# pcb_optica.net
KiCad netlist of a schematic drawn in EasyEDA Pro
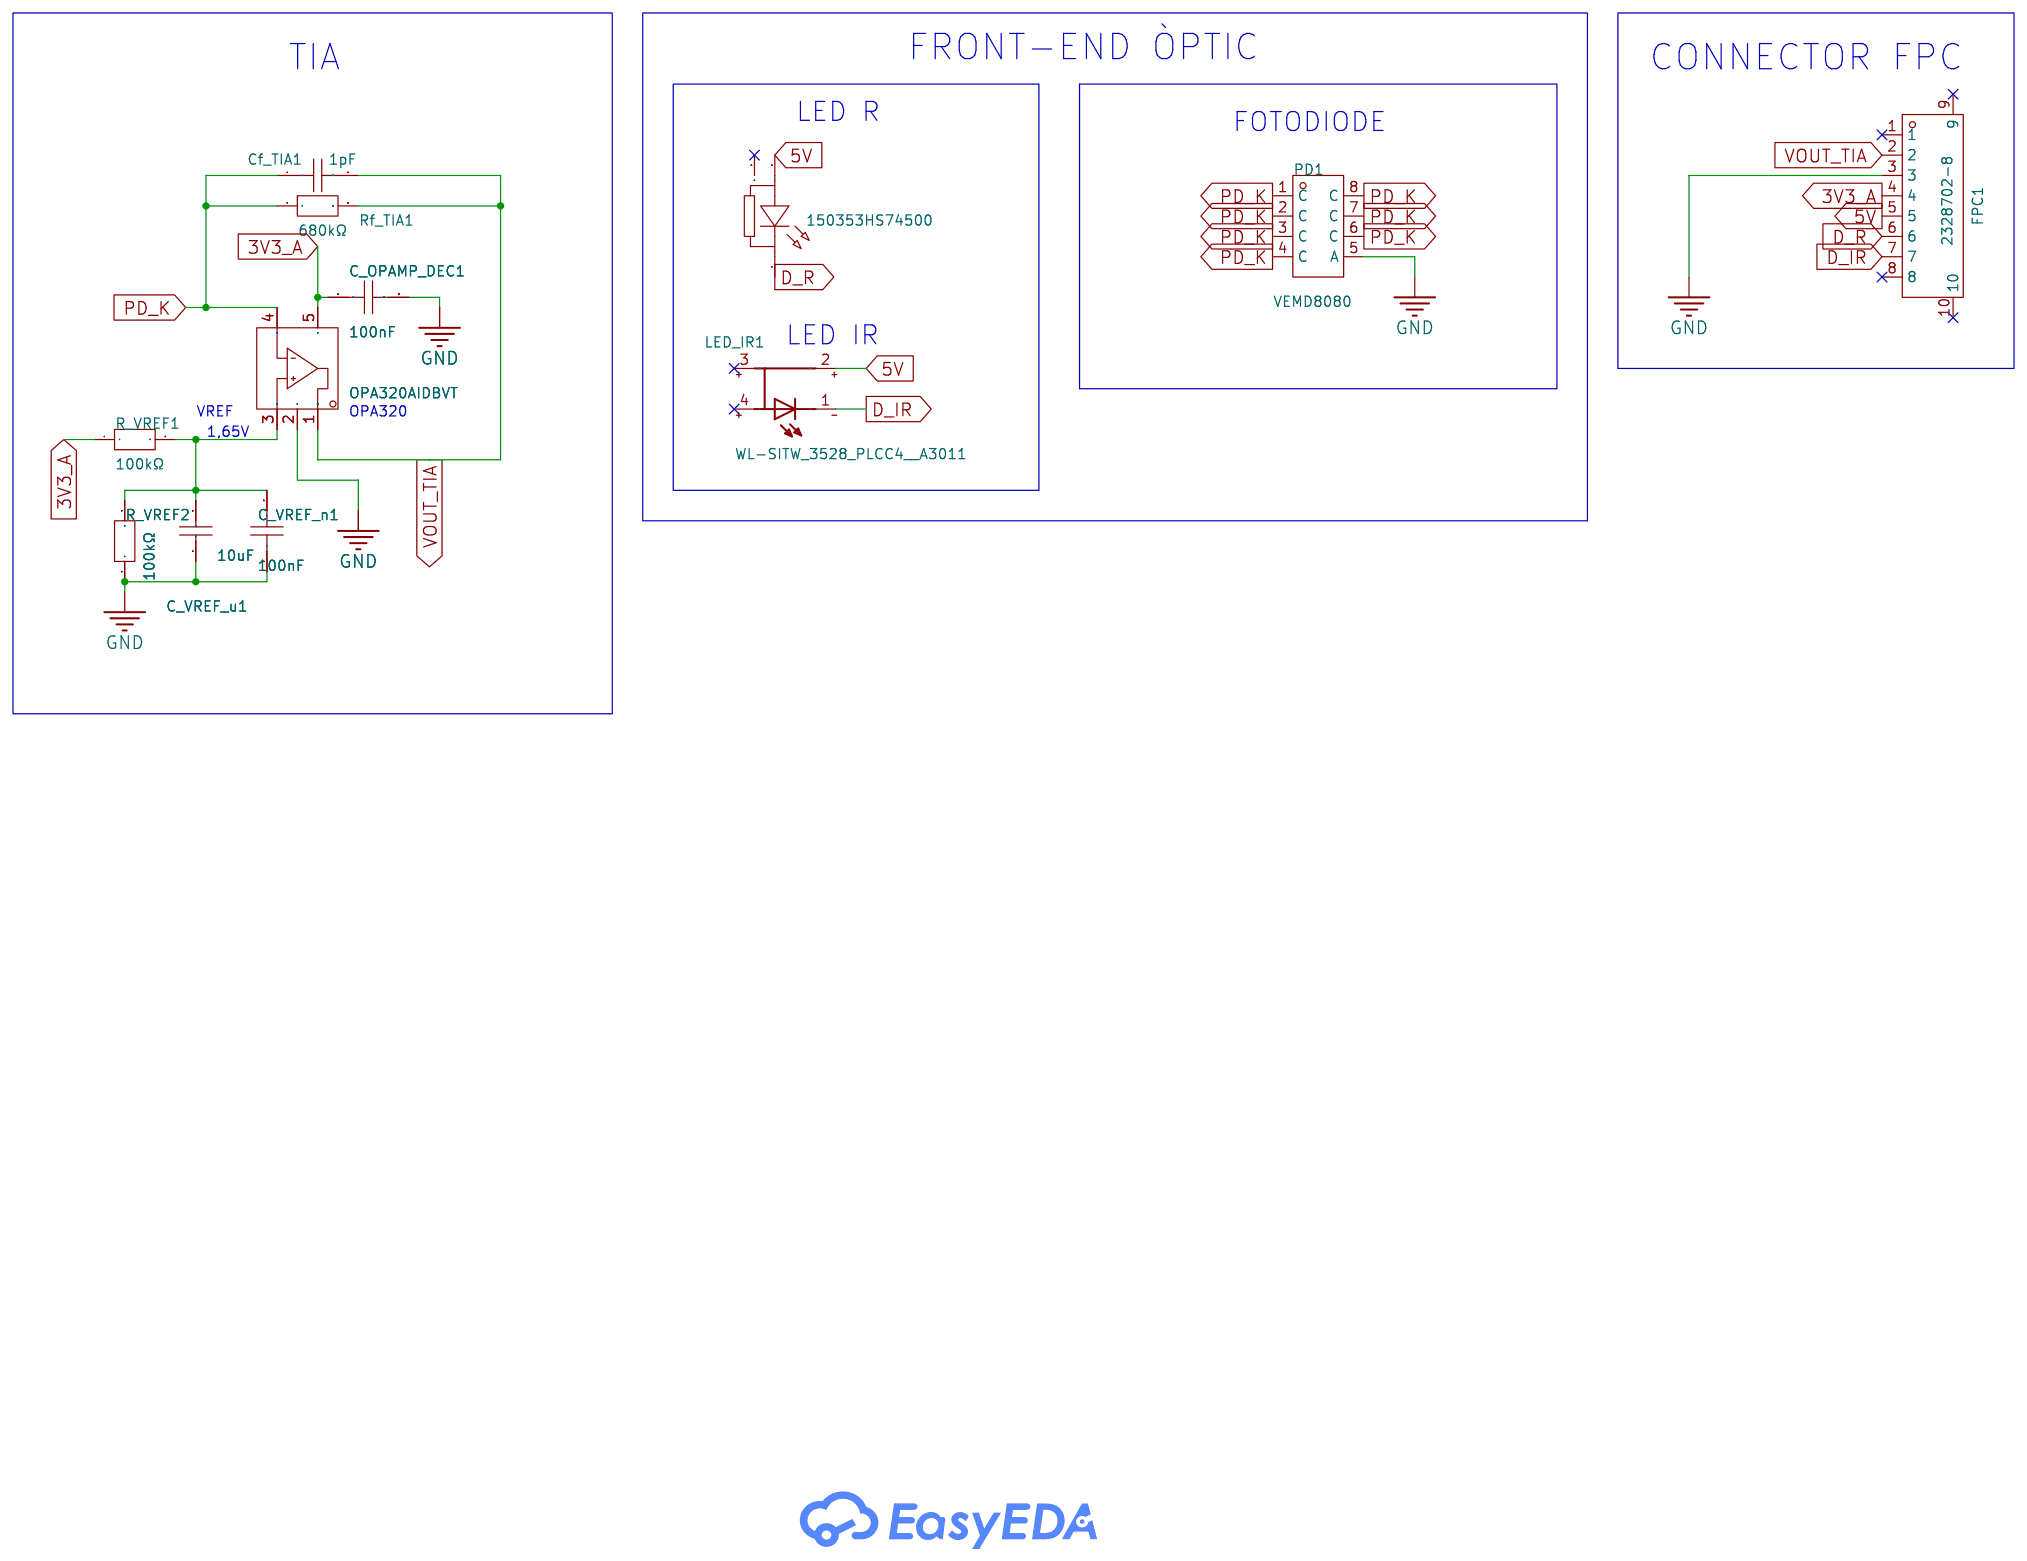
[diagram p0: schematic sheet]

(export (version "E")
  (design (tool "Eeschema 10.0.6"))
  (components
    (comp (ref "Cf_TIA1")
      (value "1pF")
      (footprint "easyedapro:C0805")
      (fields
        (field (name "Manufacturer Part") "CC0805BRNPO9BN1R0")
        (field (name "Manufacturer") "YAGEO(国巨)")
      )
      (libsource (lib "easyedapro") (part "CC0805BRNPO9BN1R0"))
    )
    (comp (ref "C_OPAMP_DEC1")
      (value "100nF")
      (footprint "easyedapro:C0805")
      (description "Capacitance:100nF Tolerance:±10% Tolerance:±10% Voltage Rating:100V Temperature Coefficient:-")
      (fields (field (name "Manufacturer Part") "C0805X104K101TB") (field (name "Manufacturer") "IHHEC(禾伸堂)"))
      (libsource (lib "easyedapro") (part "C0805X104K101TB"))
    )
    (comp (ref "C_VREF_n1")
      (value "100nF")
      (footprint "easyedapro:C0805")
      (description "Capacitance:100nF Tolerance:±10% Tolerance:±10% Voltage Rating:100V Temperature Coefficient:-")
      (fields (field (name "Manufacturer Part") "C0805X104K101TB") (field (name "Manufacturer") "IHHEC(禾伸堂)"))
      (libsource (lib "easyedapro") (part "C0805X104K101TB"))
    )
    (comp (ref "C_VREF_u1")
      (value "10uF")
      (footprint "easyedapro:C0805")
      (description "Capacitance:10uF Tolerance:±20% Tolerance:±20% Voltage Rating:10V Temperature Coefficient:Y5V")
      (fields (field (name "Manufacturer Part") "0805F106M100") (field (name "Manufacturer") "Walsin(华新科)"))
      (libsource (lib "easyedapro") (part "0805F106M100"))
    )
    (comp (ref "FPC1")
      (value "2328702-8")
      (footprint "easyedapro:CONN-SMD_8P-P0.50-2328702-8")
      (fields (field (name "Manufacturer") "TE Connectivity(泰科电子)"))
      (libsource (lib "easyedapro") (part "2328702-8"))
    )
    (comp (ref "LED_IR1")
      (value "WL-SITW_3528_PLCC4__A3011")
      (footprint "easyedapro:WL-SITW_3528_PLCC4_A3011")
      (libsource (lib "easyedapro") (part "WL-SITW_3528_PLCC4__A3011"))
    )
    (comp (ref "LED_R1")
      (value "150353HS74500")
      (footprint "easyedapro:LED-SMD_3P-L3.4-W3.4_158353050")
      (fields (field (name "Manufacturer") "Wurth(伍尔特)"))
      (libsource (lib "easyedapro") (part "150353HS74500"))
    )
    (comp (ref "PD1")
      (value "VEMD8080")
      (footprint "easyedapro:SENSOR-SMD_8P-L4.8-W2.5-P1.31")
      (fields (field (name "Manufacturer") "VISHAY(威世)"))
      (libsource (lib "easyedapro") (part "VEMD8080"))
    )
    (comp (ref "Rf_TIA1")
      (value "680kΩ")
      (footprint "easyedapro:R0805")
      (fields (field (name "Manufacturer Part") "PTFR0805B680KN9") (field (name "Manufacturer") "RESI(开步睿思)"))
      (libsource (lib "easyedapro") (part "PTFR0805B680KN9"))
    )
    (comp (ref "R_VREF1")
      (value "100kΩ")
      (footprint "easyedapro:R0603")
      (fields (field (name "Manufacturer Part") "FRC0603F1003TS") (field (name "Manufacturer") "FOJAN(富捷)"))
      (libsource (lib "easyedapro") (part "FRC0603F1003TS"))
    )
    (comp (ref "R_VREF2")
      (value "100kΩ")
      (footprint "easyedapro:R0603")
      (fields (field (name "Manufacturer Part") "FRC0603F1003TS") (field (name "Manufacturer") "FOJAN(富捷)"))
      (libsource (lib "easyedapro") (part "FRC0603F1003TS"))
    )
    (comp (ref "U_TIA1")
      (value "OPA320AIDBVT")
      (footprint "easyedapro:SOT-23-5_L2.9-W1.6-P0.95-LS2.8-BL")
      (fields (field (name "Manufacturer") "TI(德州仪器)"))
      (libsource (lib "easyedapro") (part "OPA320AIDBVT"))
    )
  )
  (nets
    (net (code "1") (name "3V3_A") (class "Default")
      (node (ref "C_OPAMP_DEC1") (pin "1") (pinfunction "1_1") (pintype "input"))
      (node (ref "FPC1") (pin "4") (pinfunction "4_4") (pintype "unspecified"))
      (node (ref "R_VREF1") (pin "1") (pinfunction "1_1") (pintype "unspecified"))
      (node (ref "U_TIA1") (pin "5") (pinfunction "V+_5") (pintype "unspecified"))
    )
    (net (code "2") (name "5V") (class "Default")
      (node (ref "FPC1") (pin "5") (pinfunction "5_5") (pintype "unspecified"))
      (node (ref "LED_IR1") (pin "2") (pinfunction "2_2") (pintype "unspecified"))
      (node (ref "LED_R1") (pin "2") (pinfunction "+_2") (pintype "unspecified"))
    )
    (net (code "3") (name "D_IR") (class "Default")
      (node (ref "FPC1") (pin "7") (pinfunction "7_7") (pintype "unspecified"))
      (node (ref "LED_IR1") (pin "1") (pinfunction "1_1") (pintype "unspecified"))
    )
    (net (code "4") (name "D_R") (class "Default")
      (node (ref "FPC1") (pin "6") (pinfunction "6_6") (pintype "unspecified"))
      (node (ref "LED_R1") (pin "1") (pinfunction "-_1") (pintype "unspecified"))
    )
    (net (code "5") (name "GND") (class "Default")
      (node (ref "C_OPAMP_DEC1") (pin "2") (pinfunction "2_2") (pintype "input"))
      (node (ref "C_VREF_n1") (pin "1") (pinfunction "1_1") (pintype "input"))
      (node (ref "C_VREF_u1") (pin "1") (pinfunction "1_1") (pintype "input"))
      (node (ref "FPC1") (pin "3") (pinfunction "3_3") (pintype "unspecified"))
      (node (ref "PD1") (pin "5") (pinfunction "A_5") (pintype "unspecified"))
      (node (ref "R_VREF2") (pin "1") (pinfunction "1_1") (pintype "unspecified"))
      (node (ref "U_TIA1") (pin "2") (pinfunction "V-_2") (pintype "unspecified"))
    )
    (net (code "6") (name "Net-(U_TIA1-IN+)") (class "Default")
      (node (ref "C_VREF_n1") (pin "2") (pinfunction "2_2") (pintype "input"))
      (node (ref "C_VREF_u1") (pin "2") (pinfunction "2_2") (pintype "input"))
      (node (ref "R_VREF1") (pin "2") (pinfunction "2_2") (pintype "unspecified"))
      (node (ref "R_VREF2") (pin "2") (pinfunction "2_2") (pintype "unspecified"))
      (node (ref "U_TIA1") (pin "3") (pinfunction "IN+_3") (pintype "unspecified"))
    )
    (net (code "7") (name "PD_K") (class "Default")
      (node (ref "Cf_TIA1") (pin "1") (pinfunction "1_1") (pintype "unspecified"))
      (node (ref "PD1") (pin "1") (pinfunction "C_1") (pintype "unspecified"))
      (node (ref "PD1") (pin "2") (pinfunction "C_2") (pintype "unspecified"))
      (node (ref "PD1") (pin "3") (pinfunction "C_3") (pintype "unspecified"))
      (node (ref "PD1") (pin "4") (pinfunction "C_4") (pintype "unspecified"))
      (node (ref "PD1") (pin "6") (pinfunction "C_6") (pintype "unspecified"))
      (node (ref "PD1") (pin "7") (pinfunction "C_7") (pintype "unspecified"))
      (node (ref "PD1") (pin "8") (pinfunction "C_8") (pintype "unspecified"))
      (node (ref "Rf_TIA1") (pin "1") (pinfunction "1_1") (pintype "unspecified"))
      (node (ref "U_TIA1") (pin "4") (pinfunction "IN-_4") (pintype "unspecified"))
    )
    (net (code "8") (name "VOUT_TIA") (class "Default")
      (node (ref "Cf_TIA1") (pin "2") (pinfunction "2_2") (pintype "unspecified"))
      (node (ref "FPC1") (pin "2") (pinfunction "2_2") (pintype "unspecified"))
      (node (ref "Rf_TIA1") (pin "2") (pinfunction "2_2") (pintype "unspecified"))
      (node (ref "U_TIA1") (pin "1") (pinfunction "OUT_1") (pintype "unspecified"))
    )
    (net (code "9") (name "unconnected-(FPC1-Pad1)") (class "Default")
      (node (ref "FPC1") (pin "1") (pinfunction "1_1") (pintype "unspecified+no_connect"))
    )
    (net (code "10") (name "unconnected-(FPC1-Pad8)") (class "Default")
      (node (ref "FPC1") (pin "8") (pinfunction "8_8") (pintype "unspecified+no_connect"))
    )
    (net (code "11") (name "unconnected-(FPC1-Pad9)") (class "Default")
      (node (ref "FPC1") (pin "9") (pinfunction "9_9") (pintype "unspecified+no_connect"))
    )
    (net (code "12") (name "unconnected-(FPC1-Pad10)") (class "Default")
      (node (ref "FPC1") (pin "10") (pinfunction "10_10") (pintype "unspecified+no_connect"))
    )
    (net (code "13") (name "unconnected-(LED_IR1-Pad3)") (class "Default")
      (node (ref "LED_IR1") (pin "3") (pinfunction "3_3") (pintype "unspecified+no_connect"))
    )
    (net (code "14") (name "unconnected-(LED_IR1-Pad4)") (class "Default")
      (node (ref "LED_IR1") (pin "4") (pinfunction "4_4") (pintype "unspecified+no_connect"))
    )
    (net (code "15") (name "unconnected-(LED_R1-Pad3)") (class "Default")
      (node (ref "LED_R1") (pin "3") (pinfunction "3_3") (pintype "unspecified+no_connect"))
    )
  )
)
